# 11_iMX_8X_SPI_ADC.net
KiCad netlist of a schematic drawn in Altium Designer
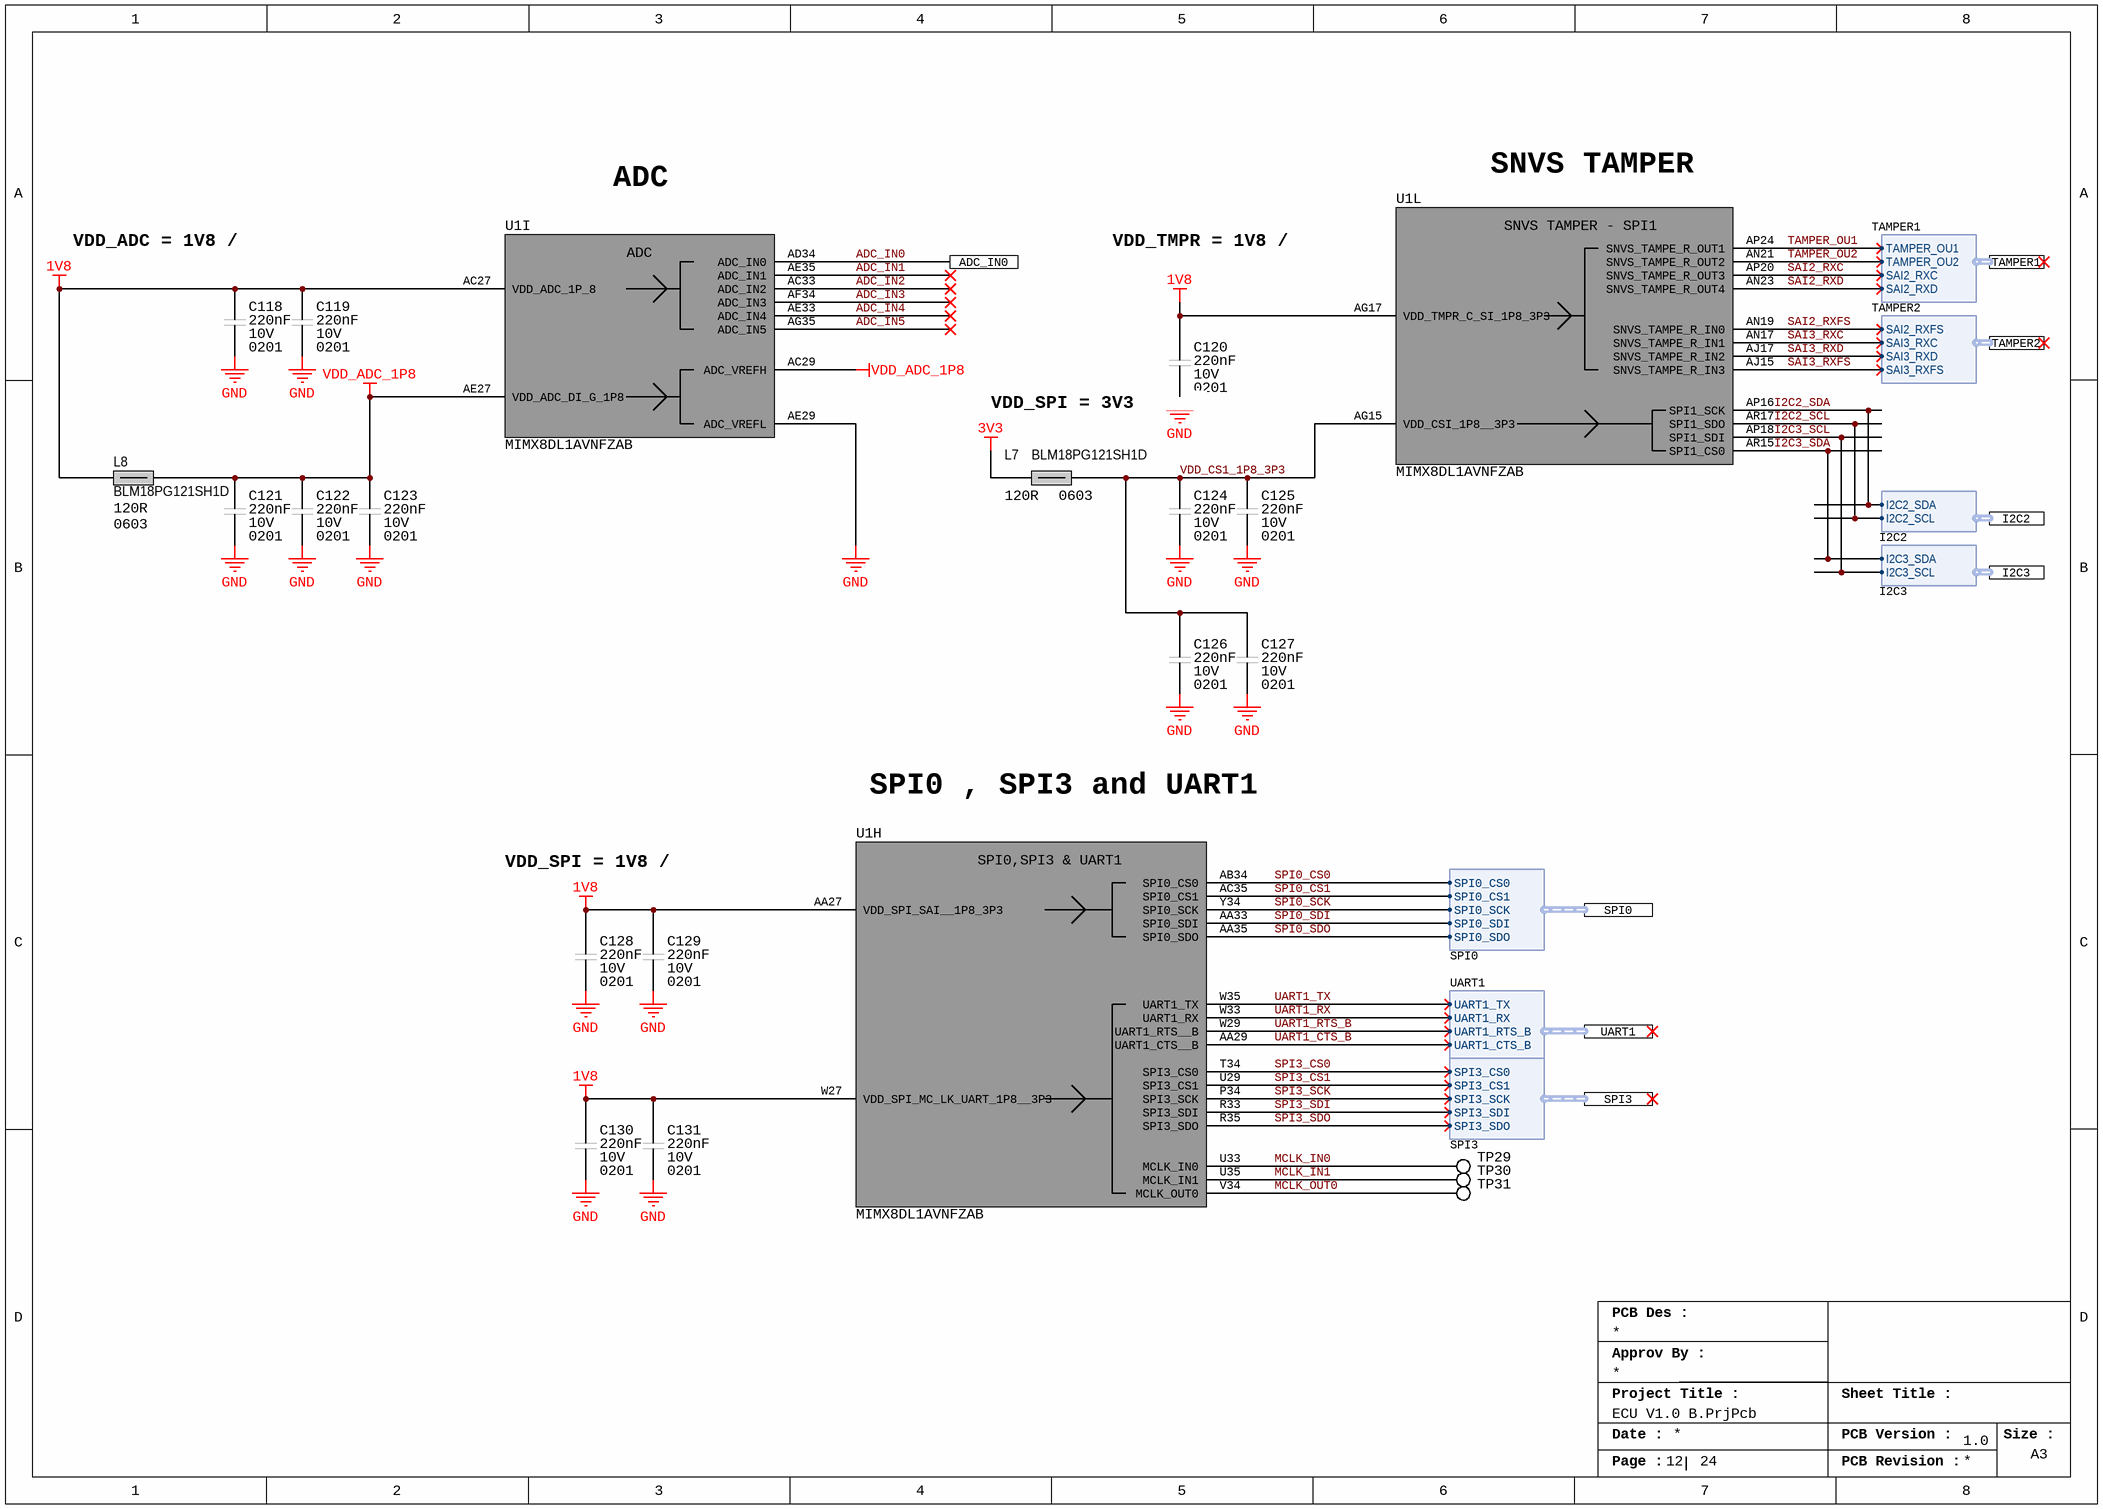
[diagram p0: 11_iMX 8X_SPI & ADC.SchDoc]

(export (version "E")
  (design (tool "Eeschema 10.0.6"))
  (components
    (comp (ref "C118")
      (value "LMK063BJ224MP-F")
      (footprint "CAP_0201_CAPC0603X03N")
      (description "Multilayer Ceramic Capacitors (High dielectric type), 10V, 0.22 uF, ± 20 %, 0201, X5R, RoHS")
      (fields
        (field (name "MANUFACTURER") "Taiyo Yuden")
        (field (name "TOLERANCE") "20%")
        (field (name "VOLTAGE RATING (DC)") "10V")
        (field (name "CAPACITANCE") "220nF")
        (field (name "CASE/PACKAGE") "0201")
      )
      (libsource (lib "Electronic Devices_LIB") (part "CAP_0.22UF_10V_X5R_0201"))
    )
    (comp (ref "C119")
      (value "LMK063BJ224MP-F")
      (footprint "CAP_0201_CAPC0603X03N")
      (description "Multilayer Ceramic Capacitors (High dielectric type), 10V, 0.22 uF, ± 20 %, 0201, X5R, RoHS")
      (fields
        (field (name "MANUFACTURER") "Taiyo Yuden")
        (field (name "TOLERANCE") "20%")
        (field (name "VOLTAGE RATING (DC)") "10V")
        (field (name "CAPACITANCE") "220nF")
        (field (name "CASE/PACKAGE") "0201")
      )
      (libsource (lib "Electronic Devices_LIB") (part "CAP_0.22UF_10V_X5R_0201"))
    )
    (comp (ref "C120")
      (value "LMK063BJ224MP-F")
      (footprint "CAP_0201_CAPC0603X03N")
      (description "Multilayer Ceramic Capacitors (High dielectric type), 10V, 0.22 uF, ± 20 %, 0201, X5R, RoHS")
      (fields
        (field (name "MANUFACTURER") "Taiyo Yuden")
        (field (name "TOLERANCE") "20%")
        (field (name "VOLTAGE RATING (DC)") "10V")
        (field (name "CAPACITANCE") "220nF")
        (field (name "CASE/PACKAGE") "0201")
      )
      (libsource (lib "Electronic Devices_LIB") (part "CAP_0.22UF_10V_X5R_0201"))
    )
    (comp (ref "C121")
      (value "LMK063BJ224MP-F")
      (footprint "CAP_0201_CAPC0603X03N")
      (description "Multilayer Ceramic Capacitors (High dielectric type), 10V, 0.22 uF, ± 20 %, 0201, X5R, RoHS")
      (fields
        (field (name "MANUFACTURER") "Taiyo Yuden")
        (field (name "TOLERANCE") "20%")
        (field (name "VOLTAGE RATING (DC)") "10V")
        (field (name "CAPACITANCE") "220nF")
        (field (name "CASE/PACKAGE") "0201")
      )
      (libsource (lib "Electronic Devices_LIB") (part "CAP_0.22UF_10V_X5R_0201"))
    )
    (comp (ref "C122")
      (value "LMK063BJ224MP-F")
      (footprint "CAP_0201_CAPC0603X03N")
      (description "Multilayer Ceramic Capacitors (High dielectric type), 10V, 0.22 uF, ± 20 %, 0201, X5R, RoHS")
      (fields
        (field (name "MANUFACTURER") "Taiyo Yuden")
        (field (name "TOLERANCE") "20%")
        (field (name "VOLTAGE RATING (DC)") "10V")
        (field (name "CAPACITANCE") "220nF")
        (field (name "CASE/PACKAGE") "0201")
      )
      (libsource (lib "Electronic Devices_LIB") (part "CAP_0.22UF_10V_X5R_0201"))
    )
    (comp (ref "C123")
      (value "LMK063BJ224MP-F")
      (footprint "CAP_0201_CAPC0603X03N")
      (description "Multilayer Ceramic Capacitors (High dielectric type), 10V, 0.22 uF, ± 20 %, 0201, X5R, RoHS")
      (fields
        (field (name "MANUFACTURER") "Taiyo Yuden")
        (field (name "TOLERANCE") "20%")
        (field (name "VOLTAGE RATING (DC)") "10V")
        (field (name "CAPACITANCE") "220nF")
        (field (name "CASE/PACKAGE") "0201")
      )
      (libsource (lib "Electronic Devices_LIB") (part "CAP_0.22UF_10V_X5R_0201"))
    )
    (comp (ref "C124")
      (value "LMK063BJ224MP-F")
      (footprint "CAP_0201_CAPC0603X03N")
      (description "Multilayer Ceramic Capacitors (High dielectric type), 10V, 0.22 uF, ± 20 %, 0201, X5R, RoHS")
      (fields
        (field (name "MANUFACTURER") "Taiyo Yuden")
        (field (name "TOLERANCE") "20%")
        (field (name "VOLTAGE RATING (DC)") "10V")
        (field (name "CAPACITANCE") "220nF")
        (field (name "CASE/PACKAGE") "0201")
      )
      (libsource (lib "Electronic Devices_LIB") (part "CAP_0.22UF_10V_X5R_0201"))
    )
    (comp (ref "C125")
      (value "LMK063BJ224MP-F")
      (footprint "CAP_0201_CAPC0603X03N")
      (description "Multilayer Ceramic Capacitors (High dielectric type), 10V, 0.22 uF, ± 20 %, 0201, X5R, RoHS")
      (fields
        (field (name "MANUFACTURER") "Taiyo Yuden")
        (field (name "TOLERANCE") "20%")
        (field (name "VOLTAGE RATING (DC)") "10V")
        (field (name "CAPACITANCE") "220nF")
        (field (name "CASE/PACKAGE") "0201")
      )
      (libsource (lib "Electronic Devices_LIB") (part "CAP_0.22UF_10V_X5R_0201"))
    )
    (comp (ref "C126")
      (value "LMK063BJ224MP-F")
      (footprint "CAP_0201_CAPC0603X03N")
      (description "Multilayer Ceramic Capacitors (High dielectric type), 10V, 0.22 uF, ± 20 %, 0201, X5R, RoHS")
      (fields
        (field (name "MANUFACTURER") "Taiyo Yuden")
        (field (name "TOLERANCE") "20%")
        (field (name "VOLTAGE RATING (DC)") "10V")
        (field (name "CAPACITANCE") "220nF")
        (field (name "CASE/PACKAGE") "0201")
      )
      (libsource (lib "Electronic Devices_LIB") (part "CAP_0.22UF_10V_X5R_0201"))
    )
    (comp (ref "C127")
      (value "LMK063BJ224MP-F")
      (footprint "CAP_0201_CAPC0603X03N")
      (description "Multilayer Ceramic Capacitors (High dielectric type), 10V, 0.22 uF, ± 20 %, 0201, X5R, RoHS")
      (fields
        (field (name "MANUFACTURER") "Taiyo Yuden")
        (field (name "TOLERANCE") "20%")
        (field (name "VOLTAGE RATING (DC)") "10V")
        (field (name "CAPACITANCE") "220nF")
        (field (name "CASE/PACKAGE") "0201")
      )
      (libsource (lib "Electronic Devices_LIB") (part "CAP_0.22UF_10V_X5R_0201"))
    )
    (comp (ref "C128")
      (value "LMK063BJ224MP-F")
      (footprint "CAP_0201_CAPC0603X03N")
      (description "Multilayer Ceramic Capacitors (High dielectric type), 10V, 0.22 uF, ± 20 %, 0201, X5R, RoHS")
      (fields
        (field (name "MANUFACTURER") "Taiyo Yuden")
        (field (name "TOLERANCE") "20%")
        (field (name "VOLTAGE RATING (DC)") "10V")
        (field (name "CAPACITANCE") "220nF")
        (field (name "CASE/PACKAGE") "0201")
      )
      (libsource (lib "Electronic Devices_LIB") (part "CAP_0.22UF_10V_X5R_0201"))
    )
    (comp (ref "C129")
      (value "LMK063BJ224MP-F")
      (footprint "CAP_0201_CAPC0603X03N")
      (description "Multilayer Ceramic Capacitors (High dielectric type), 10V, 0.22 uF, ± 20 %, 0201, X5R, RoHS")
      (fields
        (field (name "MANUFACTURER") "Taiyo Yuden")
        (field (name "TOLERANCE") "20%")
        (field (name "VOLTAGE RATING (DC)") "10V")
        (field (name "CAPACITANCE") "220nF")
        (field (name "CASE/PACKAGE") "0201")
      )
      (libsource (lib "Electronic Devices_LIB") (part "CAP_0.22UF_10V_X5R_0201"))
    )
    (comp (ref "C130")
      (value "LMK063BJ224MP-F")
      (footprint "CAP_0201_CAPC0603X03N")
      (description "Multilayer Ceramic Capacitors (High dielectric type), 10V, 0.22 uF, ± 20 %, 0201, X5R, RoHS")
      (fields
        (field (name "MANUFACTURER") "Taiyo Yuden")
        (field (name "TOLERANCE") "20%")
        (field (name "VOLTAGE RATING (DC)") "10V")
        (field (name "CAPACITANCE") "220nF")
        (field (name "CASE/PACKAGE") "0201")
      )
      (libsource (lib "Electronic Devices_LIB") (part "CAP_0.22UF_10V_X5R_0201"))
    )
    (comp (ref "C131")
      (value "LMK063BJ224MP-F")
      (footprint "CAP_0201_CAPC0603X03N")
      (description "Multilayer Ceramic Capacitors (High dielectric type), 10V, 0.22 uF, ± 20 %, 0201, X5R, RoHS")
      (fields
        (field (name "MANUFACTURER") "Taiyo Yuden")
        (field (name "TOLERANCE") "20%")
        (field (name "VOLTAGE RATING (DC)") "10V")
        (field (name "CAPACITANCE") "220nF")
        (field (name "CASE/PACKAGE") "0201")
      )
      (libsource (lib "Electronic Devices_LIB") (part "CAP_0.22UF_10V_X5R_0201"))
    )
    (comp (ref "L7")
      (value "BLM18PG121SH1D")
      (footprint "IND_0603_INDC1608X08N")
      (description "Ferrite Beads Multi-Layer 120Ohm 25% 100MHz 2A 50mOhm DCR 0603 Automotive Paper T/R")
      (fields
        (field (name "MANUFACTURER") "Murata")
        (field (name "TOLERANCE") "25%")
        (field (name "IMPEDANCE") "120R")
        (field (name "CASE/PACKAGE") "0603")
      )
      (libsource (lib "Electronic Devices_LIB") (part "IND_FERRITE_BEADS_120R_2A_0603_BLM18PG121SH1D"))
    )
    (comp (ref "L8")
      (value "BLM18PG121SH1D")
      (footprint "IND_0603_INDC1608X08N")
      (description "Ferrite Beads Multi-Layer 120Ohm 25% 100MHz 2A 50mOhm DCR 0603 Automotive Paper T/R")
      (fields
        (field (name "MANUFACTURER") "Murata")
        (field (name "TOLERANCE") "25%")
        (field (name "IMPEDANCE") "120R")
        (field (name "CASE/PACKAGE") "0603")
      )
      (libsource (lib "Electronic Devices_LIB") (part "IND_FERRITE_BEADS_120R_2A_0603_BLM18PG121SH1D"))
    )
    (comp (ref "TP29")
      (value "NO COMPONENT")
      (footprint "TP_PAD_0.5MM_SMD_ROUND")
      (description "Test Point, SMD pad, round, 1.5mm, 1.6mm, 3mm diameter")
      (libsource (lib "Electronic Devices_LIB") (part "TP_PAD_SMD_SMALL"))
    )
    (comp (ref "TP30")
      (value "NO COMPONENT")
      (footprint "TP_PAD_0.5MM_SMD_ROUND")
      (description "Test Point, SMD pad, round, 1.5mm, 1.6mm, 3mm diameter")
      (libsource (lib "Electronic Devices_LIB") (part "TP_PAD_SMD_SMALL"))
    )
    (comp (ref "TP31")
      (value "NO COMPONENT")
      (footprint "TP_PAD_0.5MM_SMD_ROUND")
      (description "Test Point, SMD pad, round, 1.5mm, 1.6mm, 3mm diameter")
      (libsource (lib "Electronic Devices_LIB") (part "TP_PAD_SMD_SMALL"))
    )
    (comp (ref "U1")
      (value "MIMX8DL1AVNFZAB")
      (footprint "MIMX8DL1AVNFZAB")
      (description "I.MX8 Dxl 15SQ / Tray Rohs Compliant: Yes")
      (fields (field (name "MANUFACTURER") "NXP Semiconductors"))
      (libsource (lib "Electronic Devices_LIB") (part "IC_MPU_ARM_1.2GHz_MIMX8DL1AVNFZAB"))
    )
  )
  (nets
    (net (code "8") (name "/ADC_IN0") (class "Default")
      (node (ref "U1") (pin "AD34") (pinfunction "ADC_IN0_AD34") (pintype "passive"))
    )
    (net (code "9") (name "/ADC_IN1") (class "Default")
      (node (ref "U1") (pin "AE35") (pinfunction "ADC_IN1_AE35") (pintype "passive+no_connect"))
    )
    (net (code "10") (name "/ADC_IN2") (class "Default")
      (node (ref "U1") (pin "AC33") (pinfunction "ADC_IN2_AC33") (pintype "passive+no_connect"))
    )
    (net (code "11") (name "/ADC_IN3") (class "Default")
      (node (ref "U1") (pin "AF34") (pinfunction "ADC_IN3_AF34") (pintype "passive+no_connect"))
    )
    (net (code "12") (name "/ADC_IN4") (class "Default")
      (node (ref "U1") (pin "AE33") (pinfunction "ADC_IN4_AE33") (pintype "passive+no_connect"))
    )
    (net (code "13") (name "/ADC_IN5") (class "Default")
      (node (ref "U1") (pin "AG35") (pinfunction "ADC_IN5_AG35") (pintype "passive+no_connect"))
    )
    (net (code "14") (name "/I2C2_SCL") (class "Default")
      (node (ref "U1") (pin "AR17") (pinfunction "SPI1_SDO_AR17") (pintype "passive"))
    )
    (net (code "15") (name "/I2C2_SDA") (class "Default")
      (node (ref "U1") (pin "AP16") (pinfunction "SPI1_SCK_AP16") (pintype "passive"))
    )
    (net (code "16") (name "/I2C3_SCL") (class "Default")
      (node (ref "U1") (pin "AP18") (pinfunction "SPI1_SDI_AP18") (pintype "passive"))
    )
    (net (code "17") (name "/I2C3_SDA") (class "Default")
      (node (ref "U1") (pin "AR15") (pinfunction "SPI1_CS0_AR15") (pintype "passive"))
    )
    (net (code "18") (name "/MCLK_IN0") (class "Default")
      (node (ref "TP29") (pin "1") (pinfunction "1_1") (pintype "passive"))
      (node (ref "U1") (pin "U33") (pinfunction "MCLK_IN0_U33") (pintype "passive"))
    )
    (net (code "19") (name "/MCLK_IN1") (class "Default")
      (node (ref "TP30") (pin "1") (pinfunction "1_1") (pintype "passive"))
      (node (ref "U1") (pin "U35") (pinfunction "MCLK_IN1_U35") (pintype "passive"))
    )
    (net (code "20") (name "/MCLK_OUT0") (class "Default")
      (node (ref "TP31") (pin "1") (pinfunction "1_1") (pintype "passive"))
      (node (ref "U1") (pin "V34") (pinfunction "MCLK_OUT0_V34") (pintype "passive"))
    )
    (net (code "21") (name "/SAI2_RXC") (class "Default")
      (node (ref "U1") (pin "AP20") (pinfunction "SNVS_TAMPE_R_OUT3_AP20") (pintype "passive+no_connect"))
    )
    (net (code "22") (name "/SAI2_RXD") (class "Default")
      (node (ref "U1") (pin "AN23") (pinfunction "SNVS_TAMPE_R_OUT4_AN23") (pintype "passive+no_connect"))
    )
    (net (code "23") (name "/SAI2_RXFS") (class "Default")
      (node (ref "U1") (pin "AN19") (pinfunction "SNVS_TAMPE_R_IN0_AN19") (pintype "passive+no_connect"))
    )
    (net (code "24") (name "/SAI3_RXC") (class "Default")
      (node (ref "U1") (pin "AN17") (pinfunction "SNVS_TAMPE_R_IN1_AN17") (pintype "passive+no_connect"))
    )
    (net (code "25") (name "/SAI3_RXD") (class "Default")
      (node (ref "U1") (pin "AJ17") (pinfunction "SNVS_TAMPE_R_IN2_AJ17") (pintype "passive+no_connect"))
    )
    (net (code "26") (name "/SAI3_RXFS") (class "Default")
      (node (ref "U1") (pin "AJ15") (pinfunction "SNVS_TAMPE_R_IN3_AJ15") (pintype "passive+no_connect"))
    )
    (net (code "27") (name "/SPI0_CS0") (class "Default")
      (node (ref "U1") (pin "AB34") (pinfunction "SPI0_CS0_AB34") (pintype "passive"))
    )
    (net (code "28") (name "/SPI0_CS1") (class "Default")
      (node (ref "U1") (pin "AC35") (pinfunction "SPI0_CS1_AC35") (pintype "passive"))
    )
    (net (code "29") (name "/SPI0_SCK") (class "Default")
      (node (ref "U1") (pin "Y34") (pinfunction "SPI0_SCK_Y34") (pintype "passive"))
    )
    (net (code "30") (name "/SPI0_SDI") (class "Default")
      (node (ref "U1") (pin "AA33") (pinfunction "SPI0_SDI_AA33") (pintype "passive"))
    )
    (net (code "31") (name "/SPI0_SDO") (class "Default")
      (node (ref "U1") (pin "AA35") (pinfunction "SPI0_SDO_AA35") (pintype "passive"))
    )
    (net (code "32") (name "/SPI3_CS0") (class "Default")
      (node (ref "U1") (pin "T34") (pinfunction "SPI3_CS0_T34") (pintype "passive+no_connect"))
    )
    (net (code "33") (name "/SPI3_CS1") (class "Default")
      (node (ref "U1") (pin "U29") (pinfunction "SPI3_CS1_U29") (pintype "passive+no_connect"))
    )
    (net (code "34") (name "/SPI3_SCK") (class "Default")
      (node (ref "U1") (pin "P34") (pinfunction "SPI3_SCK_P34") (pintype "passive+no_connect"))
    )
    (net (code "35") (name "/SPI3_SDI") (class "Default")
      (node (ref "U1") (pin "R33") (pinfunction "SPI3_SDI_R33") (pintype "passive+no_connect"))
    )
    (net (code "36") (name "/SPI3_SDO") (class "Default")
      (node (ref "U1") (pin "R35") (pinfunction "SPI3_SDO_R35") (pintype "passive+no_connect"))
    )
    (net (code "37") (name "/TAMPER_OU1") (class "Default")
      (node (ref "U1") (pin "AP24") (pinfunction "SNVS_TAMPE_R_OUT1_AP24") (pintype "passive+no_connect"))
    )
    (net (code "38") (name "/TAMPER_OU2") (class "Default")
      (node (ref "U1") (pin "AN21") (pinfunction "SNVS_TAMPE_R_OUT2_AN21") (pintype "passive+no_connect"))
    )
    (net (code "39") (name "/UART1_CTS_B") (class "Default")
      (node (ref "U1") (pin "AA29") (pinfunction "UART1_CTS__B_AA29") (pintype "passive+no_connect"))
    )
    (net (code "40") (name "/UART1_RTS_B") (class "Default")
      (node (ref "U1") (pin "W29") (pinfunction "UART1_RTS__B_W29") (pintype "passive+no_connect"))
    )
    (net (code "41") (name "/UART1_RX") (class "Default")
      (node (ref "U1") (pin "W33") (pinfunction "UART1_RX_W33") (pintype "passive+no_connect"))
    )
    (net (code "42") (name "/UART1_TX") (class "Default")
      (node (ref "U1") (pin "W35") (pinfunction "UART1_TX_W35") (pintype "passive+no_connect"))
    )
    (net (code "44") (name "/VDD_CS1_1P8_3P3") (class "Default")
      (node (ref "C124") (pin "2") (pinfunction "2_2") (pintype "passive"))
      (node (ref "C125") (pin "2") (pinfunction "2_2") (pintype "passive"))
      (node (ref "C126") (pin "2") (pinfunction "2_2") (pintype "passive"))
      (node (ref "C127") (pin "2") (pinfunction "2_2") (pintype "passive"))
      (node (ref "L7") (pin "2") (pinfunction "2_2") (pintype "passive"))
      (node (ref "U1") (pin "AG15") (pinfunction "VDD_CSI_1P8__3P3_AG15") (pintype "passive"))
    )
    (net (code "51") (name "1V8") (class "Default")
      (node (ref "C118") (pin "2") (pinfunction "2_2") (pintype "passive"))
      (node (ref "C119") (pin "2") (pinfunction "2_2") (pintype "passive"))
      (node (ref "C120") (pin "2") (pinfunction "2_2") (pintype "passive"))
      (node (ref "C128") (pin "2") (pinfunction "2_2") (pintype "passive"))
      (node (ref "C129") (pin "2") (pinfunction "2_2") (pintype "passive"))
      (node (ref "C130") (pin "2") (pinfunction "2_2") (pintype "passive"))
      (node (ref "C131") (pin "2") (pinfunction "2_2") (pintype "passive"))
      (node (ref "L8") (pin "1") (pinfunction "1_1") (pintype "passive"))
      (node (ref "U1") (pin "AA27") (pinfunction "VDD_SPI_SAI__1P8_3P3_AA27") (pintype "passive"))
      (node (ref "U1") (pin "AC27") (pinfunction "VDD_ADC_1P_8_AC27") (pintype "passive"))
      (node (ref "U1") (pin "AG17") (pinfunction "VDD_TMPR_C_SI_1P8_3P3_AG17") (pintype "passive"))
      (node (ref "U1") (pin "W27") (pinfunction "VDD_SPI_MC_LK_UART_1P8__3P3_W27") (pintype "passive"))
    )
    (net (code "52") (name "3V3") (class "Default")
      (node (ref "L7") (pin "1") (pinfunction "1_1") (pintype "passive"))
    )
    (net (code "53") (name "GND") (class "Default")
      (node (ref "C118") (pin "1") (pinfunction "1_1") (pintype "passive"))
      (node (ref "C119") (pin "1") (pinfunction "1_1") (pintype "passive"))
      (node (ref "C120") (pin "1") (pinfunction "1_1") (pintype "passive"))
      (node (ref "C121") (pin "1") (pinfunction "1_1") (pintype "passive"))
      (node (ref "C122") (pin "1") (pinfunction "1_1") (pintype "passive"))
      (node (ref "C123") (pin "1") (pinfunction "1_1") (pintype "passive"))
      (node (ref "C124") (pin "1") (pinfunction "1_1") (pintype "passive"))
      (node (ref "C125") (pin "1") (pinfunction "1_1") (pintype "passive"))
      (node (ref "C126") (pin "1") (pinfunction "1_1") (pintype "passive"))
      (node (ref "C127") (pin "1") (pinfunction "1_1") (pintype "passive"))
      (node (ref "C128") (pin "1") (pinfunction "1_1") (pintype "passive"))
      (node (ref "C129") (pin "1") (pinfunction "1_1") (pintype "passive"))
      (node (ref "C130") (pin "1") (pinfunction "1_1") (pintype "passive"))
      (node (ref "C131") (pin "1") (pinfunction "1_1") (pintype "passive"))
      (node (ref "U1") (pin "AE29") (pinfunction "ADC_VREFL_AE29") (pintype "passive"))
    )
    (net (code "54") (name "VDD_ADC_1P8") (class "Default")
      (node (ref "C121") (pin "2") (pinfunction "2_2") (pintype "passive"))
      (node (ref "C122") (pin "2") (pinfunction "2_2") (pintype "passive"))
      (node (ref "C123") (pin "2") (pinfunction "2_2") (pintype "passive"))
      (node (ref "L8") (pin "2") (pinfunction "2_2") (pintype "passive"))
      (node (ref "U1") (pin "AC29") (pinfunction "ADC_VREFH_AC29") (pintype "passive"))
      (node (ref "U1") (pin "AE27") (pinfunction "VDD_ADC_DI_G_1P8_AE27") (pintype "passive"))
    )
  )
)
